# E-15_ENET2.net
KiCad netlist of a schematic drawn in Altium Designer
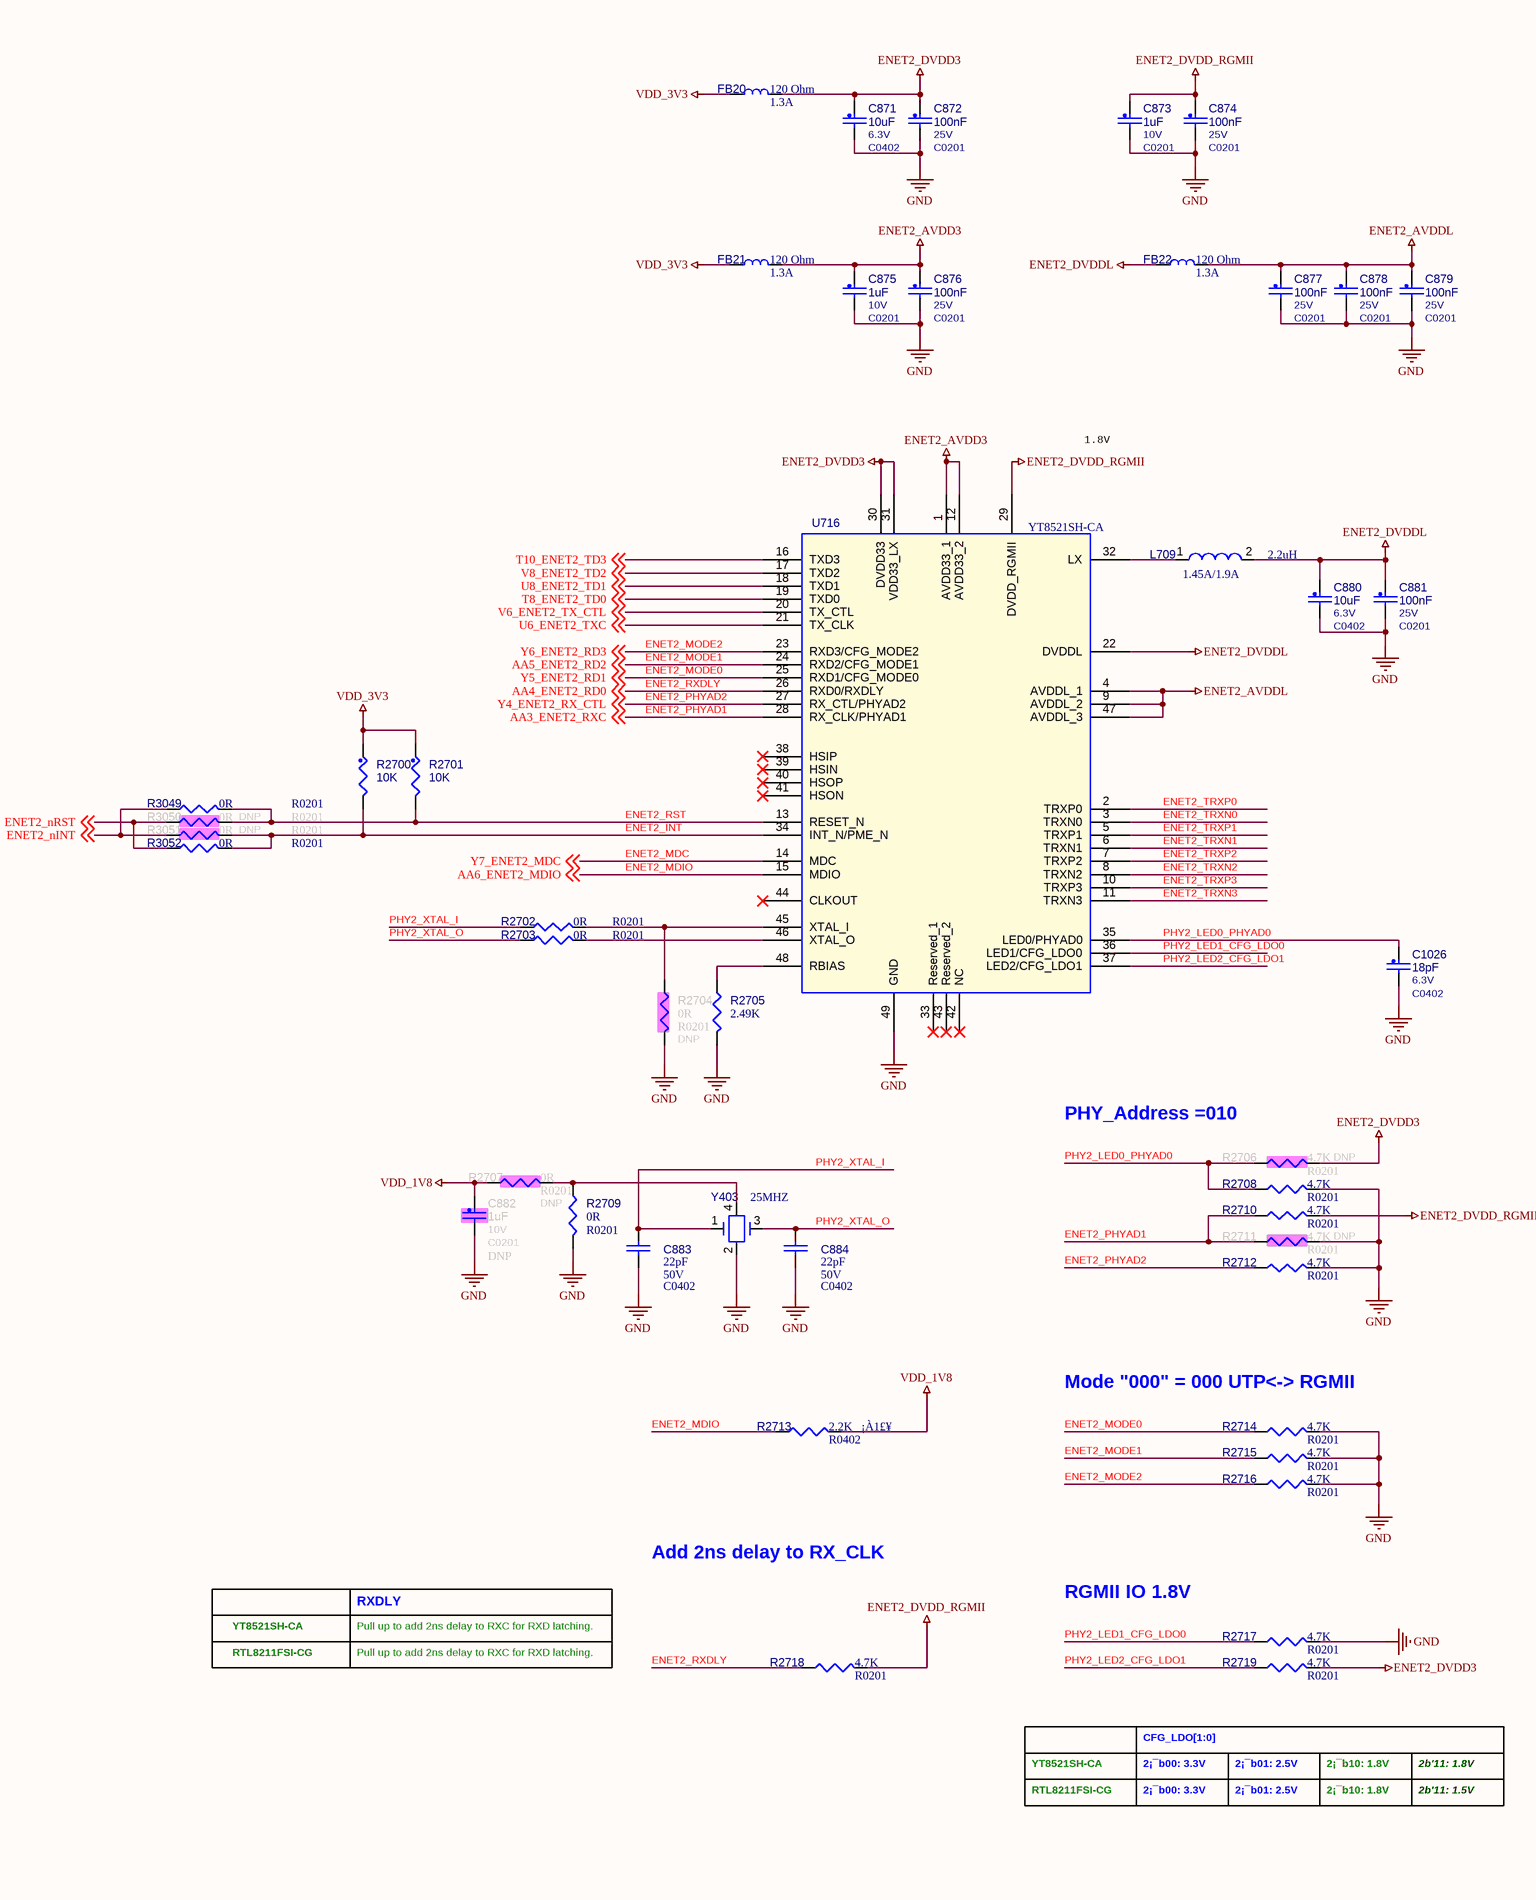
[diagram p0: E-15 ENET2.SchDoc, left]
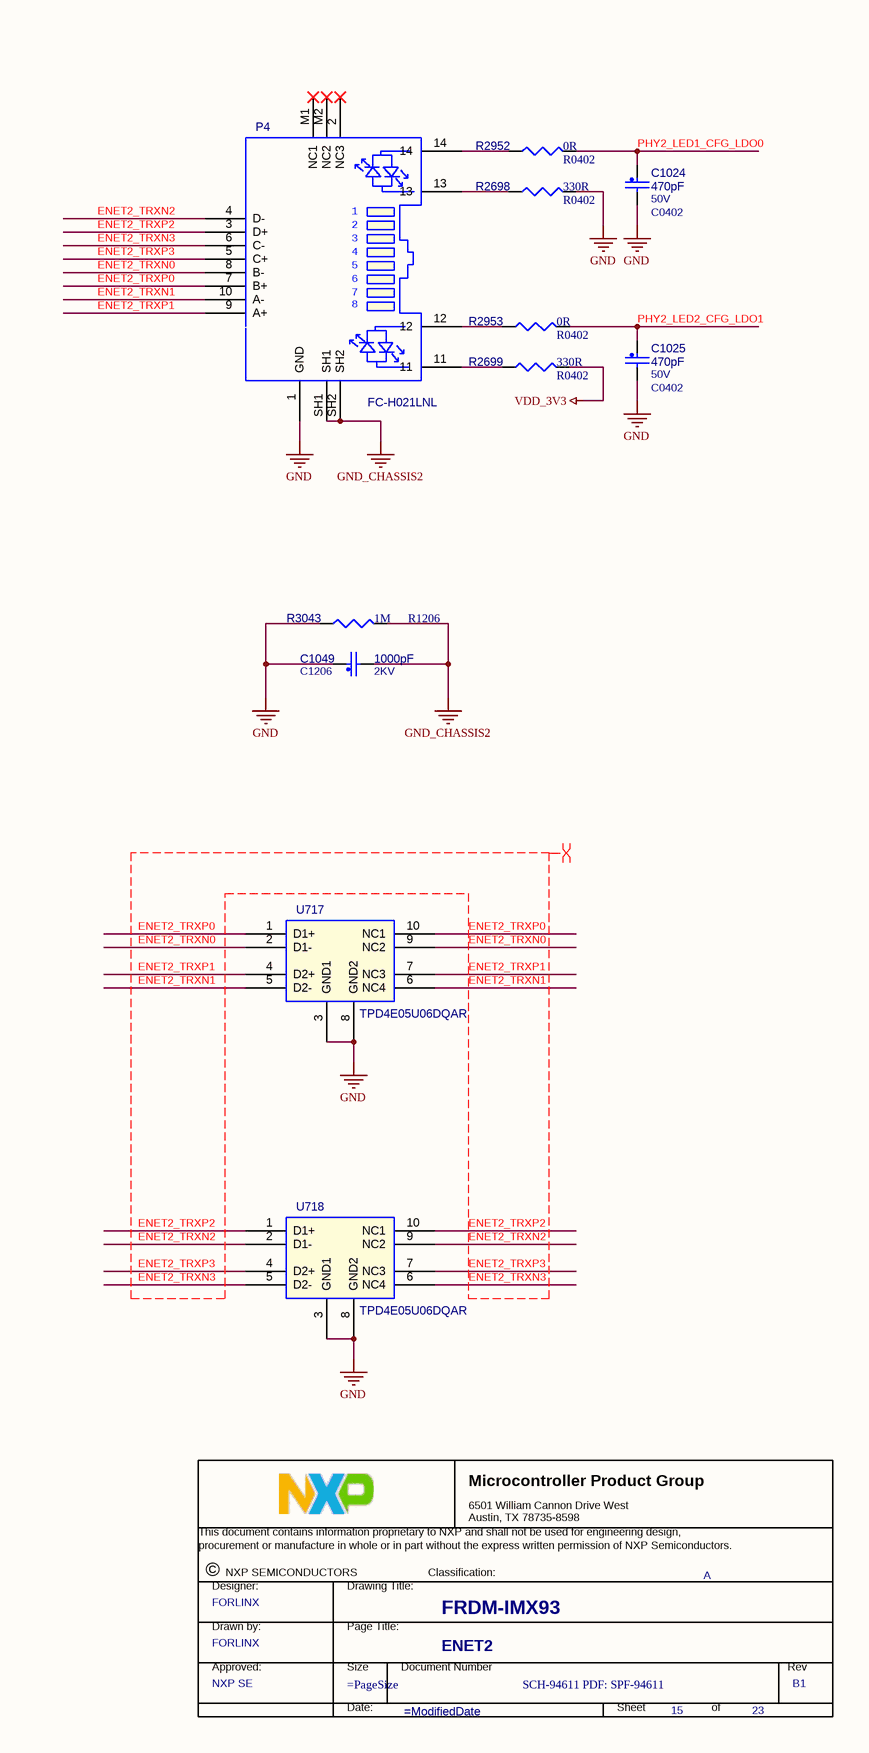
[diagram p1: E-15 ENET2.SchDoc, right]

(export (version "E")
  (design (tool "Eeschema 10.0.6"))
  (components
    (comp (ref "C871")
      (value "10uF")
      (footprint "C0402")
      (description "0402,10uF,6.3V,+/-20%,X5R")
      (fields
        (field (name "TOLERANCE") "20%")
        (field (name "VOLTAGE") "6.3V")
        (field (name "PCB FOOTPRINT") "C0402")
      )
      (libsource (lib "*") (part "CAP_NP"))
    )
    (comp (ref "C872")
      (value "100nF")
      (footprint "C0201")
      (description "0201,100nF,25V,+/-10%,X5R")
      (fields
        (field (name "VOLTAGE") "25V")
        (field (name "TOLERANCE") "20%")
        (field (name "PCB FOOTPRINT") "C0201")
      )
      (libsource (lib "*") (part "CAP_NP"))
    )
    (comp (ref "C873")
      (value "1uF")
      (footprint "C0201")
      (description "0201,1uF,10V,+/-20%,X5R")
      (fields
        (field (name "VOLTAGE") "10V")
        (field (name "TOLERANCE") "20%")
        (field (name "PCB FOOTPRINT") "C0201")
      )
      (libsource (lib "*") (part "CAP_NP"))
    )
    (comp (ref "C874")
      (value "100nF")
      (footprint "C0201")
      (description "0201,100nF,25V,+/-10%,X5R")
      (fields
        (field (name "TOLERANCE") "20%")
        (field (name "VOLTAGE") "25V")
        (field (name "PCB FOOTPRINT") "C0201")
      )
      (libsource (lib "*") (part "CAP_NP"))
    )
    (comp (ref "C875")
      (value "1uF")
      (footprint "C0201")
      (description "0201,1uF,10V,+/-20%,X5R")
      (fields
        (field (name "TOLERANCE") "20%")
        (field (name "VOLTAGE") "10V")
        (field (name "PCB FOOTPRINT") "C0201")
      )
      (libsource (lib "*") (part "CAP_NP"))
    )
    (comp (ref "C876")
      (value "100nF")
      (footprint "C0201")
      (description "0201,100nF,25V,+/-10%,X5R")
      (fields
        (field (name "VOLTAGE") "25V")
        (field (name "TOLERANCE") "20%")
        (field (name "PCB FOOTPRINT") "C0201")
      )
      (libsource (lib "*") (part "CAP_NP"))
    )
    (comp (ref "C877")
      (value "100nF")
      (footprint "C0201")
      (description "0201,100nF,25V,+/-10%,X5R")
      (fields
        (field (name "VOLTAGE") "25V")
        (field (name "TOLERANCE") "20%")
        (field (name "PCB FOOTPRINT") "C0201")
      )
      (libsource (lib "*") (part "CAP_NP"))
    )
    (comp (ref "C878")
      (value "100nF")
      (footprint "C0201")
      (description "0201,100nF,25V,+/-10%,X5R")
      (fields
        (field (name "VOLTAGE") "25V")
        (field (name "TOLERANCE") "20%")
        (field (name "PCB FOOTPRINT") "C0201")
      )
      (libsource (lib "*") (part "CAP_NP"))
    )
    (comp (ref "C879")
      (value "100nF")
      (footprint "C0201")
      (description "0201,100nF,25V,+/-10%,X5R")
      (fields
        (field (name "TOLERANCE") "20%")
        (field (name "VOLTAGE") "25V")
        (field (name "PCB FOOTPRINT") "C0201")
      )
      (libsource (lib "*") (part "CAP_NP"))
    )
    (comp (ref "C880")
      (value "10uF")
      (footprint "C0402")
      (description "0402,10uF,6.3V,+/-20%,X5R")
      (fields
        (field (name "TOLERANCE") "20%")
        (field (name "VOLTAGE") "6.3V")
        (field (name "PCB FOOTPRINT") "C0402")
      )
      (libsource (lib "*") (part "CAP_NP"))
    )
    (comp (ref "C881")
      (value "100nF")
      (footprint "C0201")
      (description "0201,100nF,25V,+/-10%,X5R")
      (fields
        (field (name "TOLERANCE") "20%")
        (field (name "VOLTAGE") "25V")
        (field (name "PCB FOOTPRINT") "C0201")
      )
      (libsource (lib "*") (part "CAP_NP"))
    )
    (comp (ref "C882")
      (value "1uF")
      (footprint "C0201")
      (description "0201,1uF,10V,+/-20%,X5R")
      (fields
        (field (name "ASSY_OPT") "DNP")
        (field (name "TOLERANCE") "20%")
        (field (name "VOLTAGE") "10V")
        (field (name "PCB FOOTPRINT") "C0201")
      )
      (libsource (lib "*") (part "CAP_NP"))
    )
    (comp (ref "C883")
      (value "22pF")
      (footprint "C0402")
      (description "0402,22pF,50V,+/-5%,NPO")
      (fields (field (name "PCB FOOTPRINT") "C0402") (field (name "VOLTAGE") "50V"))
      (libsource (lib "*") (part "C0402,22pF"))
    )
    (comp (ref "C884")
      (value "22pF")
      (footprint "C0402")
      (description "0402,22pF,50V,+/-5%,NPO")
      (fields (field (name "PCB FOOTPRINT") "C0402") (field (name "VOLTAGE") "50V"))
      (libsource (lib "*") (part "C0402,22pF"))
    )
    (comp (ref "C1024")
      (value "470pF")
      (footprint "C0402")
      (description "0402,470pF,50V,+/-5%,NPO")
      (fields
        (field (name "TOLERANCE") "20%")
        (field (name "VOLTAGE") "50V")
        (field (name "PCB FOOTPRINT") "C0402")
      )
      (libsource (lib "*") (part "CAP_NP"))
    )
    (comp (ref "C1025")
      (value "470pF")
      (footprint "C0402")
      (description "0402,470pF,50V,+/-5%,NPO")
      (fields
        (field (name "VOLTAGE") "50V")
        (field (name "TOLERANCE") "20%")
        (field (name "PCB FOOTPRINT") "C0402")
      )
      (libsource (lib "*") (part "CAP_NP"))
    )
    (comp (ref "C1026")
      (value "18pF")
      (footprint "C0402")
      (description "0402,18pF,50V,+/-5%,NPO")
      (fields
        (field (name "TOLERANCE") "20%")
        (field (name "VOLTAGE") "6.3V")
        (field (name "PCB FOOTPRINT") "C0402")
      )
      (libsource (lib "*") (part "CAP_NP"))
    )
    (comp (ref "C1049")
      (value "1000pF")
      (footprint "C1206")
      (description "1206,1nF,2KV,+/-10%")
      (fields
        (field (name "TOLERANCE") "20%")
        (field (name "VOLTAGE") "2KV")
        (field (name "PCB FOOTPRINT") "C1206")
      )
      (libsource (lib "*") (part "CAP_NP"))
    )
    (comp (ref "FB20")
      (value "120 Ohm")
      (footprint "FB0402")
      (description "0402,120Ohm@100MHz,2A")
      (fields (field (name "ELECTRIC CURRENT") "1.3A"))
      (libsource (lib "*") (part "FB0402,120ohm,1.3A"))
    )
    (comp (ref "FB21")
      (value "120 Ohm")
      (footprint "FB0402")
      (description "0402,120Ohm@100MHz,2A")
      (fields (field (name "ELECTRIC CURRENT") "1.3A"))
      (libsource (lib "*") (part "FB0402,120ohm,1.3A"))
    )
    (comp (ref "FB22")
      (value "120 Ohm")
      (footprint "FB0402")
      (description "0402,120Ohm@100MHz,2A")
      (fields (field (name "ELECTRIC CURRENT") "1.3A"))
      (libsource (lib "*") (part "FB0402,120ohm,1.3A"))
    )
    (comp (ref "L709")
      (value "2.2uH")
      (footprint "IND_2016A")
      (description "2.2uH,2*1.6*1mm,2.15A")
      (fields (field (name "ELECTRIC CURRENT") "1.45A/1.9A"))
      (libsource (lib "*") (part "INDUCTOR-WPN201612HR47MT"))
    )
    (comp (ref "P4")
      (value "FC-H021LNL")
      (footprint "RJ45-Gigabit")
      (description "HR851178A,RJ45,1000M")
      (libsource (lib "*") (part "FC-H021LNL_0"))
    )
    (comp (ref "R2698")
      (value "330R")
      (footprint "R0402")
      (description "0402,330Ohm,+/-1%")
      (fields (field (name "PCB FOOTPRINT") "R0402"))
      (libsource (lib "*") (part "R0402,4.7K_Dup1"))
    )
    (comp (ref "R2699")
      (value "330R")
      (footprint "R0402")
      (description "0402,330Ohm,+/-1%")
      (fields (field (name "PCB FOOTPRINT") "R0402"))
      (libsource (lib "*") (part "R0402,4.7K_Dup1"))
    )
    (comp (ref "R2700")
      (value "10K")
      (footprint "R0201")
      (description "0201,10K,+/-5%")
      (fields (field (name "TOLERANCE") "5%"))
      (libsource (lib "*") (part "RES"))
    )
    (comp (ref "R2701")
      (value "10K")
      (footprint "R0201")
      (description "0201,10K,+/-5%")
      (fields (field (name "TOLERANCE") "5%"))
      (libsource (lib "*") (part "RES"))
    )
    (comp (ref "R2702")
      (value "0R")
      (footprint "R0201")
      (description "0201,0Ohm,+/-5%")
      (fields (field (name "PCB FOOTPRINT") "R0201"))
      (libsource (lib "*") (part "R0402,1.5K"))
    )
    (comp (ref "R2703")
      (value "0R")
      (footprint "R0201")
      (description "0201,0Ohm,+/-5%")
      (fields (field (name "PCB FOOTPRINT") "R0201"))
      (libsource (lib "*") (part "R0402,1.5K"))
    )
    (comp (ref "R2704")
      (value "0R")
      (footprint "R0201")
      (description "0201,0Ohm,+/-5%")
      (fields (field (name "PCB FOOTPRINT") "R0201") (field (name "ASSY_OPT") "DNP"))
      (libsource (lib "*") (part "R0402,1.5K"))
    )
    (comp (ref "R2705")
      (value "2.49K")
      (footprint "R0402")
      (description "0402,2.49K,+/-1%")
      (libsource (lib "*") (part "R0402,2.49K"))
    )
    (comp (ref "R2706")
      (value "4.7K")
      (footprint "R0201")
      (description "0201,4.7K,+/-1%")
      (fields (field (name "PCB FOOTPRINT") "R0201") (field (name "ASSY_OPT") "DNP"))
      (libsource (lib "*") (part "R0402,4.7K_Dup1"))
    )
    (comp (ref "R2707")
      (value "0R")
      (footprint "R0201")
      (description "0201,0Ohm,+/-5%")
      (fields (field (name "PCB FOOTPRINT") "R0201") (field (name "ASSY_OPT") "DNP"))
      (libsource (lib "*") (part "R0402,1.5K"))
    )
    (comp (ref "R2708")
      (value "4.7K")
      (footprint "R0201")
      (description "0201,4.7K,+/-1%")
      (fields (field (name "PCB FOOTPRINT") "R0201"))
      (libsource (lib "*") (part "R0402,4.7K_Dup1"))
    )
    (comp (ref "R2709")
      (value "0R")
      (footprint "R0201")
      (description "0201,0Ohm,+/-5%")
      (fields (field (name "PCB FOOTPRINT") "R0201"))
      (libsource (lib "*") (part "R0402,1.5K"))
    )
    (comp (ref "R2710")
      (value "4.7K")
      (footprint "R0201")
      (description "0201,4.7K,+/-1%")
      (fields (field (name "PCB FOOTPRINT") "R0201"))
      (libsource (lib "*") (part "R0402,4.7K_Dup1"))
    )
    (comp (ref "R2711")
      (value "4.7K")
      (footprint "R0201")
      (description "0201,4.7K,+/-1%")
      (fields (field (name "PCB FOOTPRINT") "R0201") (field (name "ASSY_OPT") "DNP"))
      (libsource (lib "*") (part "R0402,4.7K_Dup1"))
    )
    (comp (ref "R2712")
      (value "4.7K")
      (footprint "R0201")
      (description "0201,4.7K,+/-1%")
      (fields (field (name "PCB FOOTPRINT") "R0201"))
      (libsource (lib "*") (part "R0402,4.7K_Dup1"))
    )
    (comp (ref "R2713")
      (value "2.2K")
      (footprint "R0402")
      (description "0402,2.2K,+/-1%")
      (fields (field (name "PRECISION") "±1％") (field (name "PCB FOOTPRINT") "R0402"))
      (libsource (lib "*") (part "R0402,1.5K"))
    )
    (comp (ref "R2714")
      (value "4.7K")
      (footprint "R0201")
      (description "0201,4.7K,+/-1%")
      (fields (field (name "PCB FOOTPRINT") "R0201"))
      (libsource (lib "*") (part "R0402,4.7K_Dup1"))
    )
    (comp (ref "R2715")
      (value "4.7K")
      (footprint "R0201")
      (description "0201,4.7K,+/-1%")
      (fields (field (name "PCB FOOTPRINT") "R0201"))
      (libsource (lib "*") (part "R0402,4.7K_Dup1"))
    )
    (comp (ref "R2716")
      (value "4.7K")
      (footprint "R0201")
      (description "0201,4.7K,+/-1%")
      (fields (field (name "PCB FOOTPRINT") "R0201"))
      (libsource (lib "*") (part "R0402,4.7K_Dup1"))
    )
    (comp (ref "R2717")
      (value "4.7K")
      (footprint "R0201")
      (description "0201,4.7K,+/-1%")
      (fields (field (name "PCB FOOTPRINT") "R0201"))
      (libsource (lib "*") (part "R0402,4.7K_Dup1"))
    )
    (comp (ref "R2718")
      (value "4.7K")
      (footprint "R0201")
      (description "0201,4.7K,+/-1%")
      (fields (field (name "PCB FOOTPRINT") "R0201"))
      (libsource (lib "*") (part "R0402,4.7K_Dup1"))
    )
    (comp (ref "R2719")
      (value "4.7K")
      (footprint "R0201")
      (description "0201,4.7K,+/-1%")
      (fields (field (name "PCB FOOTPRINT") "R0201"))
      (libsource (lib "*") (part "R0402,4.7K_Dup1"))
    )
    (comp (ref "R2952")
      (value "0R")
      (footprint "R0402")
      (description "0402,0Ohm,+/-1%")
      (fields (field (name "PCB FOOTPRINT") "R0402"))
      (libsource (lib "*") (part "R0402,4.7K_Dup1"))
    )
    (comp (ref "R2953")
      (value "0R")
      (footprint "R0402")
      (description "0402,0Ohm,+/-1%")
      (fields (field (name "PCB FOOTPRINT") "R0402"))
      (libsource (lib "*") (part "R0402,4.7K_Dup1"))
    )
    (comp (ref "R3043")
      (value "1M")
      (footprint "R1206")
      (description "1206,1M,+/-5%")
      (fields (field (name "PCB FOOTPRINT") "R1206"))
      (libsource (lib "*") (part "R0402,4.7K_Dup1"))
    )
    (comp (ref "R3049")
      (value "0R")
      (footprint "R0201")
      (description "0201,0Ohm,+/-5%")
      (fields (field (name "PCB FOOTPRINT") "R0201"))
      (libsource (lib "*") (part "R0402,1.5K"))
    )
    (comp (ref "R3050")
      (value "0R")
      (footprint "R0201")
      (description "0201,0Ohm,+/-5%")
      (fields (field (name "PCB FOOTPRINT") "R0201") (field (name "ASSY_OPT") "DNP"))
      (libsource (lib "*") (part "R0402,1.5K"))
    )
    (comp (ref "R3051")
      (value "0R")
      (footprint "R0201")
      (description "0201,0Ohm,+/-5%")
      (fields (field (name "PCB FOOTPRINT") "R0201") (field (name "ASSY_OPT") "DNP"))
      (libsource (lib "*") (part "R0402,1.5K"))
    )
    (comp (ref "R3052")
      (value "0R")
      (footprint "R0201")
      (description "0201,0Ohm,+/-5%")
      (fields (field (name "PCB FOOTPRINT") "R0201"))
      (libsource (lib "*") (part "R0402,1.5K"))
    )
    (comp (ref "U716")
      (value "YT8521SH-CA")
      (footprint "QFN48P_0_4BSC_6x6_H")
      (libsource (lib "*") (part "YT8521SH-CA"))
    )
    (comp (ref "U717")
      (value "TPD4E05U06DQAR")
      (footprint "USON-10")
      (description "TPD4E05U06DQAR,USON")
      (libsource (lib "*") (part "TPD4E05U06DQAR_8"))
    )
    (comp (ref "U718")
      (value "TPD4E05U06DQAR")
      (footprint "USON-10")
      (description "TPD4E05U06DQAR,USON")
      (libsource (lib "*") (part "TPD4E05U06DQAR_9"))
    )
    (comp (ref "Y403")
      (value "25MHZ")
      (footprint "xtlosc4_3p2x2p5mm_sm")
      (description "Crystal,25MHZ,4P,3.2*2.5mm,+/-20ppm,20pf")
      (libsource (lib "*") (part "CRYSTAL_4P-TSX-3225"))
    )
  )
  (nets
    (net (code "1") (name "/ENET2_INT") (class "Default")
      (node (ref "R2700") (pin "2") (pinfunction "2_2") (pintype "passive"))
      (node (ref "R3051") (pin "2") (pinfunction "2_2") (pintype "passive"))
      (node (ref "R3052") (pin "2") (pinfunction "2_2") (pintype "passive"))
      (node (ref "U716") (pin "34") (pinfunction "INT_N/PME_N_34") (pintype "passive"))
    )
    (net (code "2") (name "/ENET2_RST") (class "Default")
      (node (ref "R2701") (pin "2") (pinfunction "2_2") (pintype "passive"))
      (node (ref "R3049") (pin "2") (pinfunction "2_2") (pintype "passive"))
      (node (ref "R3050") (pin "2") (pinfunction "2_2") (pintype "passive"))
      (node (ref "U716") (pin "13") (pinfunction "RESET_N_13") (pintype "passive"))
    )
    (net (code "3") (name "/ENET2_TRXN0") (class "Default")
      (node (ref "P4") (pin "8") (pinfunction "B-_8") (pintype "passive"))
      (node (ref "U716") (pin "3") (pinfunction "TRXN0_3") (pintype "passive"))
      (node (ref "U717") (pin "2") (pinfunction "D1-_2") (pintype "passive"))
      (node (ref "U717") (pin "9") (pinfunction "NC2_9") (pintype "passive"))
    )
    (net (code "4") (name "/ENET2_TRXN1") (class "Default")
      (node (ref "P4") (pin "10") (pinfunction "A-_10") (pintype "passive"))
      (node (ref "U716") (pin "6") (pinfunction "TRXN1_6") (pintype "passive"))
      (node (ref "U717") (pin "5") (pinfunction "D2-_5") (pintype "passive"))
      (node (ref "U717") (pin "6") (pinfunction "NC4_6") (pintype "passive"))
    )
    (net (code "5") (name "/ENET2_TRXN2") (class "Default")
      (node (ref "P4") (pin "4") (pinfunction "D-_4") (pintype "passive"))
      (node (ref "U716") (pin "8") (pinfunction "TRXN2_8") (pintype "passive"))
      (node (ref "U718") (pin "2") (pinfunction "D1-_2") (pintype "passive"))
      (node (ref "U718") (pin "9") (pinfunction "NC2_9") (pintype "passive"))
    )
    (net (code "6") (name "/ENET2_TRXN3") (class "Default")
      (node (ref "P4") (pin "6") (pinfunction "C-_6") (pintype "passive"))
      (node (ref "U716") (pin "11") (pinfunction "TRXN3_11") (pintype "passive"))
      (node (ref "U718") (pin "5") (pinfunction "D2-_5") (pintype "passive"))
      (node (ref "U718") (pin "6") (pinfunction "NC4_6") (pintype "passive"))
    )
    (net (code "7") (name "/ENET2_TRXP0") (class "Default")
      (node (ref "P4") (pin "7") (pinfunction "B+_7") (pintype "passive"))
      (node (ref "U716") (pin "2") (pinfunction "TRXP0_2") (pintype "passive"))
      (node (ref "U717") (pin "1") (pinfunction "D1+_1") (pintype "passive"))
      (node (ref "U717") (pin "10") (pinfunction "NC1_10") (pintype "passive"))
    )
    (net (code "8") (name "/ENET2_TRXP1") (class "Default")
      (node (ref "P4") (pin "9") (pinfunction "A+_9") (pintype "passive"))
      (node (ref "U716") (pin "5") (pinfunction "TRXP1_5") (pintype "passive"))
      (node (ref "U717") (pin "4") (pinfunction "D2+_4") (pintype "passive"))
      (node (ref "U717") (pin "7") (pinfunction "NC3_7") (pintype "passive"))
    )
    (net (code "9") (name "/ENET2_TRXP2") (class "Default")
      (node (ref "P4") (pin "3") (pinfunction "D+_3") (pintype "passive"))
      (node (ref "U716") (pin "7") (pinfunction "TRXP2_7") (pintype "passive"))
      (node (ref "U718") (pin "1") (pinfunction "D1+_1") (pintype "passive"))
      (node (ref "U718") (pin "10") (pinfunction "NC1_10") (pintype "passive"))
    )
    (net (code "10") (name "/ENET2_TRXP3") (class "Default")
      (node (ref "P4") (pin "5") (pinfunction "C+_5") (pintype "passive"))
      (node (ref "U716") (pin "10") (pinfunction "TRXP3_10") (pintype "passive"))
      (node (ref "U718") (pin "4") (pinfunction "D2+_4") (pintype "passive"))
      (node (ref "U718") (pin "7") (pinfunction "NC3_7") (pintype "passive"))
    )
    (net (code "11") (name "/PHY2_LED0_PHYAD0") (class "Default")
      (node (ref "C1026") (pin "1") (pinfunction "1_1") (pintype "passive"))
      (node (ref "R2706") (pin "1") (pinfunction "1_1") (pintype "passive"))
      (node (ref "R2708") (pin "1") (pinfunction "1_1") (pintype "passive"))
      (node (ref "U716") (pin "35") (pinfunction "LED0/PHYAD0_35") (pintype "passive"))
    )
    (net (code "12") (name "/PHY2_LED1_CFG_LDO0") (class "Default")
      (node (ref "C1024") (pin "1") (pinfunction "1_1") (pintype "passive"))
      (node (ref "R2717") (pin "1") (pinfunction "1_1") (pintype "passive"))
      (node (ref "R2952") (pin "2") (pinfunction "2_2") (pintype "passive"))
      (node (ref "U716") (pin "36") (pinfunction "LED1/CFG_LDO0_36") (pintype "passive"))
    )
    (net (code "13") (name "/PHY2_LED2_CFG_LDO1") (class "Default")
      (node (ref "C1025") (pin "1") (pinfunction "1_1") (pintype "passive"))
      (node (ref "R2719") (pin "1") (pinfunction "1_1") (pintype "passive"))
      (node (ref "R2953") (pin "2") (pinfunction "2_2") (pintype "passive"))
      (node (ref "U716") (pin "37") (pinfunction "LED2/CFG_LDO1_37") (pintype "passive"))
    )
    (net (code "14") (name "/PHY2_XTAL_I") (class "Default")
      (node (ref "C883") (pin "1") (pinfunction "1_1") (pintype "passive"))
      (node (ref "R2702") (pin "1") (pinfunction "1_1") (pintype "passive"))
      (node (ref "Y403") (pin "1") (pinfunction "1_1") (pintype "passive"))
    )
    (net (code "15") (name "/PHY2_XTAL_O") (class "Default")
      (node (ref "C884") (pin "1") (pinfunction "1_1") (pintype "passive"))
      (node (ref "R2703") (pin "1") (pinfunction "1_1") (pintype "passive"))
      (node (ref "Y403") (pin "3") (pinfunction "3_3") (pintype "passive"))
    )
    (net (code "16") (name "AA3_ENET2_RXC") (class "Default")
      (node (ref "R2710") (pin "1") (pinfunction "1_1") (pintype "passive"))
      (node (ref "R2711") (pin "1") (pinfunction "1_1") (pintype "passive"))
      (node (ref "U716") (pin "28") (pinfunction "RX_CLK/PHYAD1_28") (pintype "passive"))
    )
    (net (code "17") (name "AA4_ENET2_RD0") (class "Default")
      (node (ref "R2718") (pin "1") (pinfunction "1_1") (pintype "passive"))
      (node (ref "U716") (pin "26") (pinfunction "RXD0/RXDLY_26") (pintype "passive"))
    )
    (net (code "18") (name "AA5_ENET2_RD2") (class "Default")
      (node (ref "R2715") (pin "1") (pinfunction "1_1") (pintype "passive"))
      (node (ref "U716") (pin "24") (pinfunction "RXD2/CFG_MODE1_24") (pintype "passive"))
    )
    (net (code "19") (name "AA6_ENET2_MDIO") (class "Default")
      (node (ref "R2713") (pin "1") (pinfunction "1_1") (pintype "passive"))
      (node (ref "U716") (pin "15") (pinfunction "MDIO_15") (pintype "passive"))
    )
    (net (code "20") (name "ENET2_AVDD3") (class "Default")
      (node (ref "C875") (pin "1") (pinfunction "1_1") (pintype "passive"))
      (node (ref "C876") (pin "1") (pinfunction "1_1") (pintype "passive"))
      (node (ref "FB21") (pin "2") (pinfunction "2_2") (pintype "passive"))
      (node (ref "U716") (pin "1") (pinfunction "AVDD33_1_1") (pintype "passive"))
      (node (ref "U716") (pin "12") (pinfunction "AVDD33_2_12") (pintype "passive"))
    )
    (net (code "21") (name "ENET2_AVDDL") (class "Default")
      (node (ref "C877") (pin "1") (pinfunction "1_1") (pintype "passive"))
      (node (ref "C878") (pin "1") (pinfunction "1_1") (pintype "passive"))
      (node (ref "C879") (pin "1") (pinfunction "1_1") (pintype "passive"))
      (node (ref "FB22") (pin "2") (pinfunction "2_2") (pintype "passive"))
      (node (ref "U716") (pin "4") (pinfunction "AVDDL_1_4") (pintype "passive"))
      (node (ref "U716") (pin "47") (pinfunction "AVDDL_3_47") (pintype "passive"))
      (node (ref "U716") (pin "9") (pinfunction "AVDDL_2_9") (pintype "passive"))
    )
    (net (code "22") (name "ENET2_DVDD3") (class "Default")
      (node (ref "C871") (pin "1") (pinfunction "1_1") (pintype "passive"))
      (node (ref "C872") (pin "1") (pinfunction "1_1") (pintype "passive"))
      (node (ref "FB20") (pin "2") (pinfunction "2_2") (pintype "passive"))
      (node (ref "R2706") (pin "2") (pinfunction "2_2") (pintype "passive"))
      (node (ref "R2719") (pin "2") (pinfunction "2_2") (pintype "passive"))
      (node (ref "U716") (pin "30") (pinfunction "DVDD33_30") (pintype "passive"))
      (node (ref "U716") (pin "31") (pinfunction "VDD33_LX_31") (pintype "passive"))
    )
    (net (code "23") (name "ENET2_DVDDL") (class "Default")
      (node (ref "C880") (pin "1") (pinfunction "1_1") (pintype "passive"))
      (node (ref "C881") (pin "1") (pinfunction "1_1") (pintype "passive"))
      (node (ref "FB22") (pin "1") (pinfunction "1_1") (pintype "passive"))
      (node (ref "L709") (pin "2") (pinfunction "2_2") (pintype "passive"))
      (node (ref "U716") (pin "22") (pinfunction "DVDDL_22") (pintype "passive"))
    )
    (net (code "24") (name "ENET2_DVDD_RGMII") (class "Default")
      (node (ref "C873") (pin "1") (pinfunction "1_1") (pintype "passive"))
      (node (ref "C874") (pin "1") (pinfunction "1_1") (pintype "passive"))
      (node (ref "R2710") (pin "2") (pinfunction "2_2") (pintype "passive"))
      (node (ref "R2718") (pin "2") (pinfunction "2_2") (pintype "passive"))
      (node (ref "U716") (pin "29") (pinfunction "DVDD_RGMII_29") (pintype "passive"))
    )
    (net (code "25") (name "ENET2_nINT") (class "Default")
      (node (ref "R3049") (pin "1") (pinfunction "1_1") (pintype "passive"))
      (node (ref "R3051") (pin "1") (pinfunction "1_1") (pintype "passive"))
    )
    (net (code "26") (name "ENET2_nRST") (class "Default")
      (node (ref "R3050") (pin "1") (pinfunction "1_1") (pintype "passive"))
      (node (ref "R3052") (pin "1") (pinfunction "1_1") (pintype "passive"))
    )
    (net (code "27") (name "GND") (class "Default")
      (node (ref "C1024") (pin "2") (pinfunction "2_2") (pintype "passive"))
      (node (ref "C1025") (pin "2") (pinfunction "2_2") (pintype "passive"))
      (node (ref "C1026") (pin "2") (pinfunction "2_2") (pintype "passive"))
      (node (ref "C1049") (pin "1") (pinfunction "1_1") (pintype "passive"))
      (node (ref "C871") (pin "2") (pinfunction "2_2") (pintype "passive"))
      (node (ref "C872") (pin "2") (pinfunction "2_2") (pintype "passive"))
      (node (ref "C873") (pin "2") (pinfunction "2_2") (pintype "passive"))
      (node (ref "C874") (pin "2") (pinfunction "2_2") (pintype "passive"))
      (node (ref "C875") (pin "2") (pinfunction "2_2") (pintype "passive"))
      (node (ref "C876") (pin "2") (pinfunction "2_2") (pintype "passive"))
      (node (ref "C877") (pin "2") (pinfunction "2_2") (pintype "passive"))
      (node (ref "C878") (pin "2") (pinfunction "2_2") (pintype "passive"))
      (node (ref "C879") (pin "2") (pinfunction "2_2") (pintype "passive"))
      (node (ref "C880") (pin "2") (pinfunction "2_2") (pintype "passive"))
      (node (ref "C881") (pin "2") (pinfunction "2_2") (pintype "passive"))
      (node (ref "C882") (pin "2") (pinfunction "2_2") (pintype "passive"))
      (node (ref "C883") (pin "2") (pinfunction "2_2") (pintype "passive"))
      (node (ref "C884") (pin "2") (pinfunction "2_2") (pintype "passive"))
      (node (ref "P4") (pin "1") (pinfunction "GND_1") (pintype "power_in"))
      (node (ref "R2698") (pin "2") (pinfunction "2_2") (pintype "passive"))
      (node (ref "R2704") (pin "2") (pinfunction "2_2") (pintype "passive"))
      (node (ref "R2705") (pin "2") (pinfunction "2_2") (pintype "passive"))
      (node (ref "R2708") (pin "2") (pinfunction "2_2") (pintype "passive"))
      (node (ref "R2709") (pin "2") (pinfunction "2_2") (pintype "passive"))
      (node (ref "R2711") (pin "2") (pinfunction "2_2") (pintype "passive"))
      (node (ref "R2712") (pin "2") (pinfunction "2_2") (pintype "passive"))
      (node (ref "R2714") (pin "2") (pinfunction "2_2") (pintype "passive"))
      (node (ref "R2715") (pin "2") (pinfunction "2_2") (pintype "passive"))
      (node (ref "R2716") (pin "2") (pinfunction "2_2") (pintype "passive"))
      (node (ref "R2717") (pin "2") (pinfunction "2_2") (pintype "passive"))
      (node (ref "R3043") (pin "1") (pinfunction "1_1") (pintype "passive"))
      (node (ref "U716") (pin "49") (pinfunction "GND_49") (pintype "passive"))
      (node (ref "U717") (pin "3") (pinfunction "GND1_3") (pintype "passive"))
      (node (ref "U717") (pin "8") (pinfunction "GND2_8") (pintype "passive"))
      (node (ref "U718") (pin "3") (pinfunction "GND1_3") (pintype "passive"))
      (node (ref "U718") (pin "8") (pinfunction "GND2_8") (pintype "passive"))
      (node (ref "Y403") (pin "2") (pinfunction "2_2") (pintype "passive"))
    )
    (net (code "28") (name "GND_CHASSIS2") (class "Default")
      (node (ref "C1049") (pin "2") (pinfunction "2_2") (pintype "passive"))
      (node (ref "P4") (pin "SH1") (pinfunction "SH1_SH1") (pintype "passive"))
      (node (ref "P4") (pin "SH2") (pinfunction "SH2_SH2") (pintype "passive"))
      (node (ref "R3043") (pin "2") (pinfunction "2_2") (pintype "passive"))
    )
    (net (code "29") (name "Net-(P4-Pad11)") (class "Default")
      (node (ref "P4") (pin "11") (pinfunction "11_11") (pintype "passive"))
      (node (ref "R2699") (pin "1") (pinfunction "1_1") (pintype "passive"))
    )
    (net (code "30") (name "Net-(P4-Pad12)") (class "Default")
      (node (ref "P4") (pin "12") (pinfunction "12_12") (pintype "passive"))
      (node (ref "R2953") (pin "1") (pinfunction "1_1") (pintype "passive"))
    )
    (net (code "31") (name "Net-(P4-Pad13)") (class "Default")
      (node (ref "P4") (pin "13") (pinfunction "13_13") (pintype "passive"))
      (node (ref "R2698") (pin "1") (pinfunction "1_1") (pintype "passive"))
    )
    (net (code "32") (name "Net-(P4-Pad14)") (class "Default")
      (node (ref "P4") (pin "14") (pinfunction "14_14") (pintype "passive"))
      (node (ref "R2952") (pin "1") (pinfunction "1_1") (pintype "passive"))
    )
    (net (code "33") (name "Net-(R2707-Pad2)") (class "Default")
      (node (ref "R2707") (pin "2") (pinfunction "2_2") (pintype "passive"))
      (node (ref "R2709") (pin "1") (pinfunction "1_1") (pintype "passive"))
      (node (ref "Y403") (pin "4") (pinfunction "4_4") (pintype "passive"))
    )
    (net (code "34") (name "Net-(U716-LX)") (class "Default")
      (node (ref "L709") (pin "1") (pinfunction "1_1") (pintype "passive"))
      (node (ref "U716") (pin "32") (pinfunction "LX_32") (pintype "passive"))
    )
    (net (code "35") (name "Net-(U716-RBIAS)") (class "Default")
      (node (ref "R2705") (pin "1") (pinfunction "1_1") (pintype "passive"))
      (node (ref "U716") (pin "48") (pinfunction "RBIAS_48") (pintype "passive"))
    )
    (net (code "36") (name "Net-(U716-XTAL_I)") (class "Default")
      (node (ref "R2702") (pin "2") (pinfunction "2_2") (pintype "passive"))
      (node (ref "R2704") (pin "1") (pinfunction "1_1") (pintype "passive"))
      (node (ref "U716") (pin "45") (pinfunction "XTAL_I_45") (pintype "passive"))
    )
    (net (code "37") (name "Net-(U716-XTAL_O)") (class "Default")
      (node (ref "R2703") (pin "2") (pinfunction "2_2") (pintype "passive"))
      (node (ref "U716") (pin "46") (pinfunction "XTAL_O_46") (pintype "passive"))
    )
    (net (code "38") (name "T8_ENET2_TD0") (class "Default")
      (node (ref "U716") (pin "19") (pinfunction "TXD0_19") (pintype "passive"))
    )
    (net (code "39") (name "T10_ENET2_TD3") (class "Default")
      (node (ref "U716") (pin "16") (pinfunction "TXD3_16") (pintype "passive"))
    )
    (net (code "40") (name "U6_ENET2_TXC") (class "Default")
      (node (ref "U716") (pin "21") (pinfunction "TX_CLK_21") (pintype "passive"))
    )
    (net (code "41") (name "U8_ENET2_TD1") (class "Default")
      (node (ref "U716") (pin "18") (pinfunction "TXD1_18") (pintype "passive"))
    )
    (net (code "42") (name "V6_ENET2_TX_CTL") (class "Default")
      (node (ref "U716") (pin "20") (pinfunction "TX_CTL_20") (pintype "passive"))
    )
    (net (code "43") (name "V8_ENET2_TD2") (class "Default")
      (node (ref "U716") (pin "17") (pinfunction "TXD2_17") (pintype "passive"))
    )
    (net (code "44") (name "VDD_1V8") (class "Default")
      (node (ref "C882") (pin "1") (pinfunction "1_1") (pintype "passive"))
      (node (ref "R2707") (pin "1") (pinfunction "1_1") (pintype "passive"))
      (node (ref "R2713") (pin "2") (pinfunction "2_2") (pintype "passive"))
    )
    (net (code "45") (name "VDD_3V3") (class "Default")
      (node (ref "FB20") (pin "1") (pinfunction "1_1") (pintype "passive"))
      (node (ref "FB21") (pin "1") (pinfunction "1_1") (pintype "passive"))
      (node (ref "R2699") (pin "2") (pinfunction "2_2") (pintype "passive"))
      (node (ref "R2700") (pin "1") (pinfunction "1_1") (pintype "passive"))
      (node (ref "R2701") (pin "1") (pinfunction "1_1") (pintype "passive"))
    )
    (net (code "46") (name "Y4_ENET2_RX_CTL") (class "Default")
      (node (ref "R2712") (pin "1") (pinfunction "1_1") (pintype "passive"))
      (node (ref "U716") (pin "27") (pinfunction "RX_CTL/PHYAD2_27") (pintype "passive"))
    )
    (net (code "47") (name "Y5_ENET2_RD1") (class "Default")
      (node (ref "R2714") (pin "1") (pinfunction "1_1") (pintype "passive"))
      (node (ref "U716") (pin "25") (pinfunction "RXD1/CFG_MODE0_25") (pintype "passive"))
    )
    (net (code "48") (name "Y6_ENET2_RD3") (class "Default")
      (node (ref "R2716") (pin "1") (pinfunction "1_1") (pintype "passive"))
      (node (ref "U716") (pin "23") (pinfunction "RXD3/CFG_MODE2_23") (pintype "passive"))
    )
    (net (code "49") (name "Y7_ENET2_MDC") (class "Default")
      (node (ref "U716") (pin "14") (pinfunction "MDC_14") (pintype "passive"))
    )
    (net (code "50") (name "unconnected-(P4-NC1-PadM1)") (class "Default")
      (node (ref "P4") (pin "M1") (pinfunction "NC1_M1") (pintype "passive+no_connect"))
    )
    (net (code "51") (name "unconnected-(P4-NC2-PadM2)") (class "Default")
      (node (ref "P4") (pin "M2") (pinfunction "NC2_M2") (pintype "passive+no_connect"))
    )
    (net (code "52") (name "unconnected-(P4-NC3-Pad2)") (class "Default")
      (node (ref "P4") (pin "2") (pinfunction "NC3_2") (pintype "passive+no_connect"))
    )
    (net (code "53") (name "unconnected-(U716-CLKOUT-Pad44)") (class "Default")
      (node (ref "U716") (pin "44") (pinfunction "CLKOUT_44") (pintype "passive+no_connect"))
    )
    (net (code "54") (name "unconnected-(U716-HSIN-Pad39)") (class "Default")
      (node (ref "U716") (pin "39") (pinfunction "HSIN_39") (pintype "passive+no_connect"))
    )
    (net (code "55") (name "unconnected-(U716-HSIP-Pad38)") (class "Default")
      (node (ref "U716") (pin "38") (pinfunction "HSIP_38") (pintype "passive+no_connect"))
    )
    (net (code "56") (name "unconnected-(U716-HSON-Pad41)") (class "Default")
      (node (ref "U716") (pin "41") (pinfunction "HSON_41") (pintype "passive+no_connect"))
    )
    (net (code "57") (name "unconnected-(U716-HSOP-Pad40)") (class "Default")
      (node (ref "U716") (pin "40") (pinfunction "HSOP_40") (pintype "passive+no_connect"))
    )
    (net (code "58") (name "unconnected-(U716-NC-Pad42)") (class "Default")
      (node (ref "U716") (pin "42") (pinfunction "NC_42") (pintype "passive+no_connect"))
    )
    (net (code "59") (name "unconnected-(U716-Reserved_1-Pad33)") (class "Default")
      (node (ref "U716") (pin "33") (pinfunction "Reserved_1_33") (pintype "passive+no_connect"))
    )
    (net (code "60") (name "unconnected-(U716-Reserved_2-Pad43)") (class "Default")
      (node (ref "U716") (pin "43") (pinfunction "Reserved_2_43") (pintype "passive+no_connect"))
    )
  )
)
